# ProPrj_USBuddy_2026-05-01.net
KiCad netlist of a schematic drawn in EasyEDA Pro
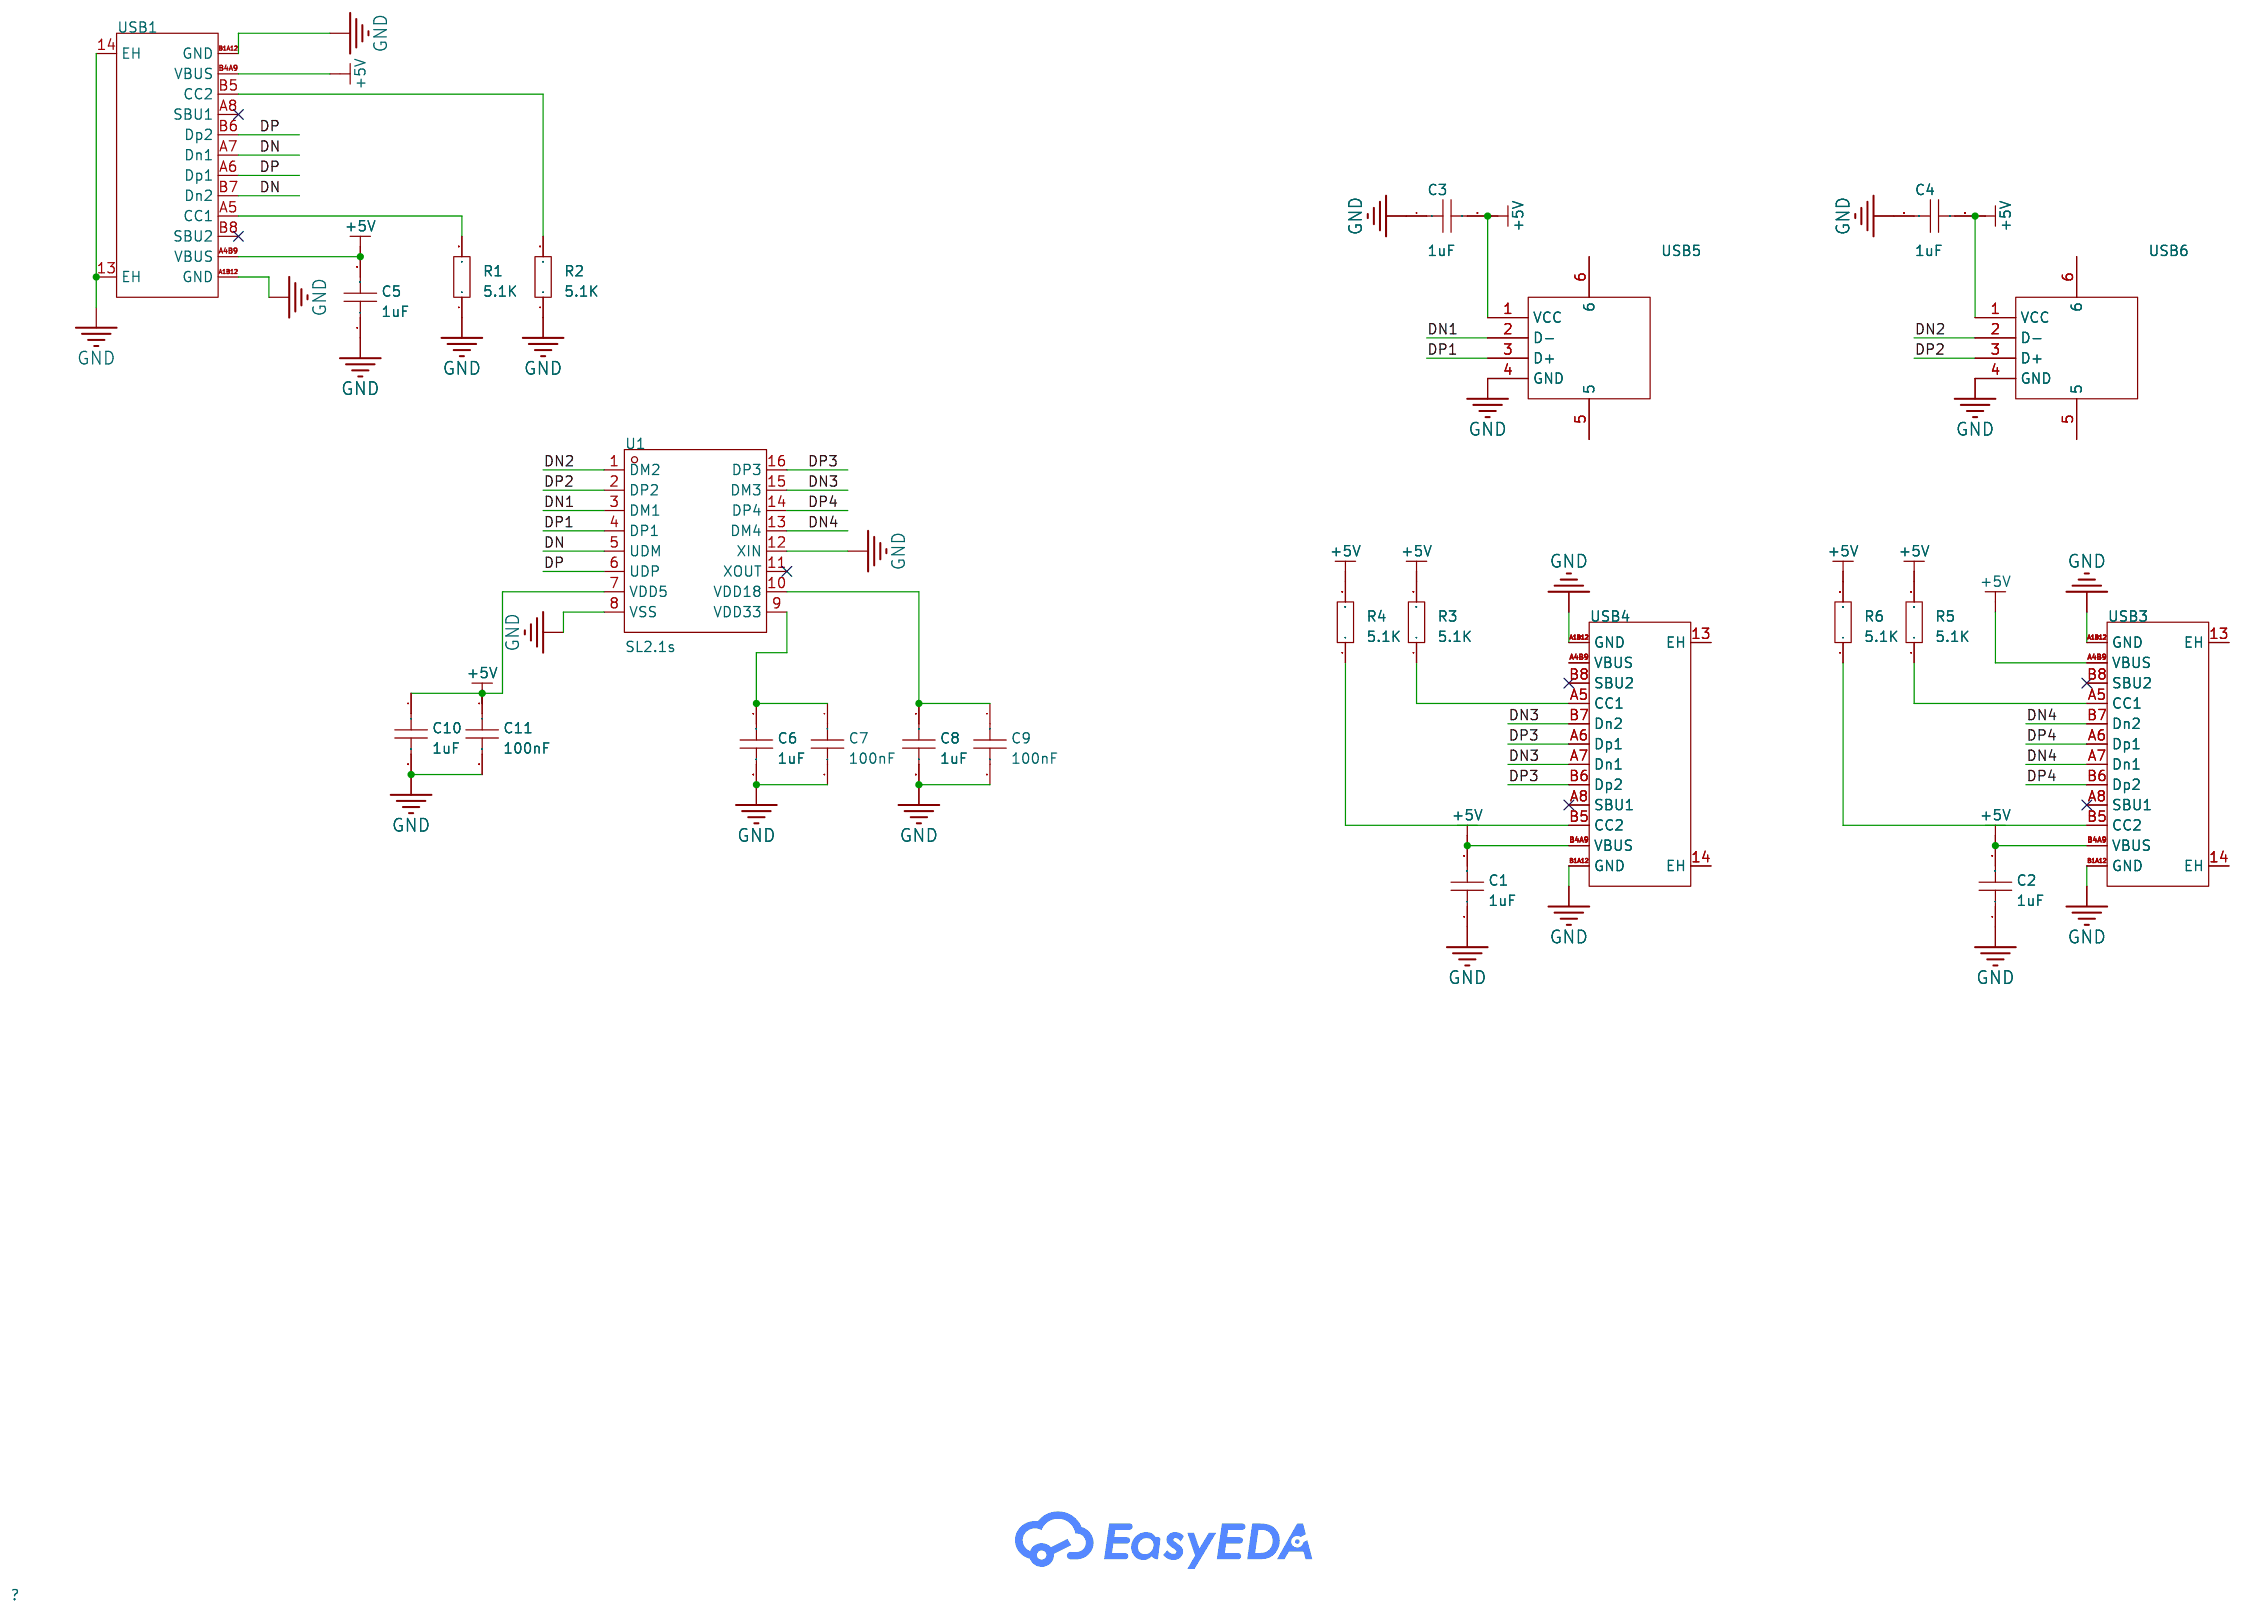
[diagram p0: schematic sheet]

(export (version "E")
  (design (tool "Eeschema 10.0.6"))
  (components
    (comp (ref "C1") (value "1uF") (footprint "easyedapro:C0603") (libsource (lib "easyedapro") (part "CAP")))
    (comp (ref "C2") (value "1uF") (footprint "easyedapro:C0603") (libsource (lib "easyedapro") (part "CAP")))
    (comp (ref "C3") (value "1uF") (footprint "easyedapro:C0603") (libsource (lib "easyedapro") (part "CAP")))
    (comp (ref "C4") (value "1uF") (footprint "easyedapro:C0603") (libsource (lib "easyedapro") (part "CAP")))
    (comp (ref "C5") (value "1uF") (footprint "easyedapro:C0603") (libsource (lib "easyedapro") (part "CAP")))
    (comp (ref "C6") (value "1uF") (footprint "easyedapro:C0603") (libsource (lib "easyedapro") (part "CAP")))
    (comp (ref "C7")
      (value "100nF")
      (footprint "easyedapro:C0603")
      (libsource (lib "easyedapro") (part "CAP"))
    )
    (comp (ref "C8") (value "1uF") (footprint "easyedapro:C0603") (libsource (lib "easyedapro") (part "CAP")))
    (comp (ref "C9")
      (value "100nF")
      (footprint "easyedapro:C0603")
      (libsource (lib "easyedapro") (part "CAP"))
    )
    (comp (ref "C10")
      (value "1uF")
      (footprint "easyedapro:C0603")
      (libsource (lib "easyedapro") (part "CAP"))
    )
    (comp (ref "C11")
      (value "100nF")
      (footprint "easyedapro:C0603")
      (libsource (lib "easyedapro") (part "CAP"))
    )
    (comp (ref "R1")
      (value "5.1K")
      (footprint "easyedapro:R0603")
      (libsource (lib "easyedapro") (part "Res"))
    )
    (comp (ref "R2")
      (value "5.1K")
      (footprint "easyedapro:R0603")
      (libsource (lib "easyedapro") (part "Res"))
    )
    (comp (ref "R3")
      (value "5.1K")
      (footprint "easyedapro:R0603")
      (libsource (lib "easyedapro") (part "Res"))
    )
    (comp (ref "R4")
      (value "5.1K")
      (footprint "easyedapro:R0603")
      (libsource (lib "easyedapro") (part "Res"))
    )
    (comp (ref "R5")
      (value "5.1K")
      (footprint "easyedapro:R0603")
      (libsource (lib "easyedapro") (part "Res"))
    )
    (comp (ref "R6")
      (value "5.1K")
      (footprint "easyedapro:R0603")
      (libsource (lib "easyedapro") (part "Res"))
    )
    (comp (ref "U1")
      (value "SL2.1s")
      (footprint "easyedapro:SSOP-16_L4.6-W2.6-P0.53-LS4.0-BL")
      (fields (field (name "Manufacturer") "CoreChips(和芯润德)"))
      (libsource (lib "easyedapro") (part "SL2.1S"))
    )
    (comp (ref "USB1")
      (value "TYPE-C 16PIN 2MD(073)")
      (footprint "easyedapro:USB-C-SMD_TYPE-C-16PIN-2MD-073")
      (fields (field (name "Manufacturer") "SHOU HAN(首韩)"))
      (libsource (lib "easyedapro") (part "TYPE-C 16PIN 2MD(073)"))
    )
    (comp (ref "USB3")
      (value "TYPE-C 16PIN 2MD(073)")
      (footprint "easyedapro:USB-C-SMD_TYPE-C-16PIN-2MD-073")
      (fields (field (name "Manufacturer") "SHOU HAN(首韩)"))
      (libsource (lib "easyedapro") (part "TYPE-C 16PIN 2MD(073)"))
    )
    (comp (ref "USB4")
      (value "TYPE-C 16PIN 2MD(073)")
      (footprint "easyedapro:USB-C-SMD_TYPE-C-16PIN-2MD-073")
      (fields (field (name "Manufacturer") "SHOU HAN(首韩)"))
      (libsource (lib "easyedapro") (part "TYPE-C 16PIN 2MD(073)"))
    )
    (comp (ref "USB5")
      (value "10.0 QHHTZB6.3")
      (footprint "easyedapro:USB-A-TH_10.0QHHTZB6.3")
      (fields (field (name "Manufacturer") "SHOU HAN(首韩)"))
      (libsource (lib "easyedapro") (part "10.0 QHHTZB6.3"))
    )
    (comp (ref "USB6")
      (value "10.0 QHHTZB6.3")
      (footprint "easyedapro:USB-A-TH_10.0QHHTZB6.3")
      (fields (field (name "Manufacturer") "SHOU HAN(首韩)"))
      (libsource (lib "easyedapro") (part "10.0 QHHTZB6.3"))
    )
  )
  (nets
    (net (code "1") (name "+5V") (class "Default")
      (node (ref "C1") (pin "2") (pinfunction "2_2") (pintype "input"))
      (node (ref "C10") (pin "1") (pinfunction "1_1") (pintype "input"))
      (node (ref "C11") (pin "1") (pinfunction "1_1") (pintype "input"))
      (node (ref "C2") (pin "2") (pinfunction "2_2") (pintype "input"))
      (node (ref "C3") (pin "2") (pinfunction "2_2") (pintype "input"))
      (node (ref "C4") (pin "2") (pinfunction "2_2") (pintype "input"))
      (node (ref "C5") (pin "2") (pinfunction "2_2") (pintype "input"))
      (node (ref "R3") (pin "2") (pinfunction "2_2") (pintype "input"))
      (node (ref "R4") (pin "2") (pinfunction "2_2") (pintype "input"))
      (node (ref "R5") (pin "2") (pinfunction "2_2") (pintype "input"))
      (node (ref "R6") (pin "2") (pinfunction "2_2") (pintype "input"))
      (node (ref "U1") (pin "7") (pinfunction "VDD5_7") (pintype "unspecified"))
      (node (ref "USB1") (pin "A4B9") (pinfunction "VBUS_A4B9") (pintype "unspecified"))
      (node (ref "USB1") (pin "B4A9") (pinfunction "VBUS_B4A9") (pintype "unspecified"))
      (node (ref "USB3") (pin "A4B9") (pinfunction "VBUS_A4B9") (pintype "unspecified"))
      (node (ref "USB3") (pin "B4A9") (pinfunction "VBUS_B4A9") (pintype "unspecified"))
      (node (ref "USB4") (pin "B4A9") (pinfunction "VBUS_B4A9") (pintype "unspecified"))
      (node (ref "USB5") (pin "1") (pinfunction "VCC_1") (pintype "unspecified"))
      (node (ref "USB6") (pin "1") (pinfunction "VCC_1") (pintype "unspecified"))
    )
    (net (code "2") (name "/DN") (class "Default")
      (node (ref "U1") (pin "5") (pinfunction "UDM_5") (pintype "unspecified"))
      (node (ref "USB1") (pin "A7") (pinfunction "Dn1_A7") (pintype "unspecified"))
      (node (ref "USB1") (pin "B7") (pinfunction "Dn2_B7") (pintype "unspecified"))
    )
    (net (code "3") (name "/DN1") (class "Default")
      (node (ref "U1") (pin "3") (pinfunction "DM1_3") (pintype "unspecified"))
      (node (ref "USB5") (pin "2") (pinfunction "D-_2") (pintype "unspecified"))
    )
    (net (code "4") (name "/DN2") (class "Default")
      (node (ref "U1") (pin "1") (pinfunction "DM2_1") (pintype "unspecified"))
      (node (ref "USB6") (pin "2") (pinfunction "D-_2") (pintype "unspecified"))
    )
    (net (code "5") (name "/DN3") (class "Default")
      (node (ref "U1") (pin "15") (pinfunction "DM3_15") (pintype "unspecified"))
      (node (ref "USB4") (pin "A7") (pinfunction "Dn1_A7") (pintype "unspecified"))
      (node (ref "USB4") (pin "B7") (pinfunction "Dn2_B7") (pintype "unspecified"))
    )
    (net (code "6") (name "/DN4") (class "Default")
      (node (ref "U1") (pin "13") (pinfunction "DM4_13") (pintype "unspecified"))
      (node (ref "USB3") (pin "A7") (pinfunction "Dn1_A7") (pintype "unspecified"))
      (node (ref "USB3") (pin "B7") (pinfunction "Dn2_B7") (pintype "unspecified"))
    )
    (net (code "7") (name "/DP") (class "Default")
      (node (ref "U1") (pin "6") (pinfunction "UDP_6") (pintype "unspecified"))
      (node (ref "USB1") (pin "A6") (pinfunction "Dp1_A6") (pintype "unspecified"))
      (node (ref "USB1") (pin "B6") (pinfunction "Dp2_B6") (pintype "unspecified"))
    )
    (net (code "8") (name "/DP1") (class "Default")
      (node (ref "U1") (pin "4") (pinfunction "DP1_4") (pintype "unspecified"))
      (node (ref "USB5") (pin "3") (pinfunction "D+_3") (pintype "unspecified"))
    )
    (net (code "9") (name "/DP2") (class "Default")
      (node (ref "U1") (pin "2") (pinfunction "DP2_2") (pintype "unspecified"))
      (node (ref "USB6") (pin "3") (pinfunction "D+_3") (pintype "unspecified"))
    )
    (net (code "10") (name "/DP3") (class "Default")
      (node (ref "U1") (pin "16") (pinfunction "DP3_16") (pintype "unspecified"))
      (node (ref "USB4") (pin "A6") (pinfunction "Dp1_A6") (pintype "unspecified"))
      (node (ref "USB4") (pin "B6") (pinfunction "Dp2_B6") (pintype "unspecified"))
    )
    (net (code "11") (name "/DP4") (class "Default")
      (node (ref "U1") (pin "14") (pinfunction "DP4_14") (pintype "unspecified"))
      (node (ref "USB3") (pin "A6") (pinfunction "Dp1_A6") (pintype "unspecified"))
      (node (ref "USB3") (pin "B6") (pinfunction "Dp2_B6") (pintype "unspecified"))
    )
    (net (code "12") (name "GND") (class "Default")
      (node (ref "C1") (pin "1") (pinfunction "1_1") (pintype "input"))
      (node (ref "C10") (pin "2") (pinfunction "2_2") (pintype "input"))
      (node (ref "C11") (pin "2") (pinfunction "2_2") (pintype "input"))
      (node (ref "C2") (pin "1") (pinfunction "1_1") (pintype "input"))
      (node (ref "C3") (pin "1") (pinfunction "1_1") (pintype "input"))
      (node (ref "C4") (pin "1") (pinfunction "1_1") (pintype "input"))
      (node (ref "C5") (pin "1") (pinfunction "1_1") (pintype "input"))
      (node (ref "C6") (pin "2") (pinfunction "2_2") (pintype "input"))
      (node (ref "C7") (pin "2") (pinfunction "2_2") (pintype "input"))
      (node (ref "C8") (pin "2") (pinfunction "2_2") (pintype "input"))
      (node (ref "C9") (pin "2") (pinfunction "2_2") (pintype "input"))
      (node (ref "R1") (pin "1") (pinfunction "1_1") (pintype "input"))
      (node (ref "R2") (pin "1") (pinfunction "1_1") (pintype "input"))
      (node (ref "U1") (pin "12") (pinfunction "XIN_12") (pintype "unspecified"))
      (node (ref "U1") (pin "8") (pinfunction "VSS_8") (pintype "unspecified"))
      (node (ref "USB1") (pin "13") (pinfunction "EH_13") (pintype "unspecified"))
      (node (ref "USB1") (pin "14") (pinfunction "EH_14") (pintype "unspecified"))
      (node (ref "USB1") (pin "A1B12") (pinfunction "GND_A1B12") (pintype "unspecified"))
      (node (ref "USB1") (pin "B1A12") (pinfunction "GND_B1A12") (pintype "unspecified"))
      (node (ref "USB3") (pin "A1B12") (pinfunction "GND_A1B12") (pintype "unspecified"))
      (node (ref "USB3") (pin "B1A12") (pinfunction "GND_B1A12") (pintype "unspecified"))
      (node (ref "USB4") (pin "A1B12") (pinfunction "GND_A1B12") (pintype "unspecified"))
      (node (ref "USB4") (pin "B1A12") (pinfunction "GND_B1A12") (pintype "unspecified"))
      (node (ref "USB5") (pin "4") (pinfunction "GND_4") (pintype "unspecified"))
      (node (ref "USB6") (pin "4") (pinfunction "GND_4") (pintype "unspecified"))
    )
    (net (code "13") (name "Net-(U1-VDD18)") (class "Default")
      (node (ref "C8") (pin "1") (pinfunction "1_1") (pintype "input"))
      (node (ref "C9") (pin "1") (pinfunction "1_1") (pintype "input"))
      (node (ref "U1") (pin "10") (pinfunction "VDD18_10") (pintype "unspecified"))
    )
    (net (code "14") (name "Net-(U1-VDD33)") (class "Default")
      (node (ref "C6") (pin "1") (pinfunction "1_1") (pintype "input"))
      (node (ref "C7") (pin "1") (pinfunction "1_1") (pintype "input"))
      (node (ref "U1") (pin "9") (pinfunction "VDD33_9") (pintype "unspecified"))
    )
    (net (code "15") (name "Net-(USB1-CC1)") (class "Default")
      (node (ref "R1") (pin "2") (pinfunction "2_2") (pintype "input"))
      (node (ref "USB1") (pin "A5") (pinfunction "CC1_A5") (pintype "unspecified"))
    )
    (net (code "16") (name "Net-(USB1-CC2)") (class "Default")
      (node (ref "R2") (pin "2") (pinfunction "2_2") (pintype "input"))
      (node (ref "USB1") (pin "B5") (pinfunction "CC2_B5") (pintype "unspecified"))
    )
    (net (code "17") (name "Net-(USB3-CC1)") (class "Default")
      (node (ref "R5") (pin "1") (pinfunction "1_1") (pintype "input"))
      (node (ref "USB3") (pin "A5") (pinfunction "CC1_A5") (pintype "unspecified"))
    )
    (net (code "18") (name "Net-(USB3-CC2)") (class "Default")
      (node (ref "R6") (pin "1") (pinfunction "1_1") (pintype "input"))
      (node (ref "USB3") (pin "B5") (pinfunction "CC2_B5") (pintype "unspecified"))
    )
    (net (code "19") (name "Net-(USB4-CC1)") (class "Default")
      (node (ref "R3") (pin "1") (pinfunction "1_1") (pintype "input"))
      (node (ref "USB4") (pin "A5") (pinfunction "CC1_A5") (pintype "unspecified"))
    )
    (net (code "20") (name "Net-(USB4-CC2)") (class "Default")
      (node (ref "R4") (pin "1") (pinfunction "1_1") (pintype "input"))
      (node (ref "USB4") (pin "B5") (pinfunction "CC2_B5") (pintype "unspecified"))
    )
    (net (code "21") (name "unconnected-(U1-XOUT-Pad11)") (class "Default")
      (node (ref "U1") (pin "11") (pinfunction "XOUT_11") (pintype "unspecified+no_connect"))
    )
    (net (code "22") (name "unconnected-(USB1-SBU1-PadA8)") (class "Default")
      (node (ref "USB1") (pin "A8") (pinfunction "SBU1_A8") (pintype "unspecified+no_connect"))
    )
    (net (code "23") (name "unconnected-(USB1-SBU2-PadB8)") (class "Default")
      (node (ref "USB1") (pin "B8") (pinfunction "SBU2_B8") (pintype "unspecified+no_connect"))
    )
    (net (code "24") (name "unconnected-(USB3-EH-Pad13)") (class "Default")
      (node (ref "USB3") (pin "13") (pinfunction "EH_13") (pintype "unspecified"))
    )
    (net (code "25") (name "unconnected-(USB3-EH-Pad14)") (class "Default")
      (node (ref "USB3") (pin "14") (pinfunction "EH_14") (pintype "unspecified"))
    )
    (net (code "26") (name "unconnected-(USB3-SBU1-PadA8)") (class "Default")
      (node (ref "USB3") (pin "A8") (pinfunction "SBU1_A8") (pintype "unspecified+no_connect"))
    )
    (net (code "27") (name "unconnected-(USB3-SBU2-PadB8)") (class "Default")
      (node (ref "USB3") (pin "B8") (pinfunction "SBU2_B8") (pintype "unspecified+no_connect"))
    )
    (net (code "28") (name "unconnected-(USB4-EH-Pad13)") (class "Default")
      (node (ref "USB4") (pin "13") (pinfunction "EH_13") (pintype "unspecified"))
    )
    (net (code "29") (name "unconnected-(USB4-EH-Pad14)") (class "Default")
      (node (ref "USB4") (pin "14") (pinfunction "EH_14") (pintype "unspecified"))
    )
    (net (code "30") (name "unconnected-(USB4-SBU1-PadA8)") (class "Default")
      (node (ref "USB4") (pin "A8") (pinfunction "SBU1_A8") (pintype "unspecified+no_connect"))
    )
    (net (code "31") (name "unconnected-(USB4-SBU2-PadB8)") (class "Default")
      (node (ref "USB4") (pin "B8") (pinfunction "SBU2_B8") (pintype "unspecified+no_connect"))
    )
    (net (code "32") (name "unconnected-(USB4-VBUS-PadA4B9)") (class "Default")
      (node (ref "USB4") (pin "A4B9") (pinfunction "VBUS_A4B9") (pintype "unspecified"))
    )
    (net (code "33") (name "unconnected-(USB5-Pad5)") (class "Default")
      (node (ref "USB5") (pin "5") (pinfunction "5_5") (pintype "unspecified"))
    )
    (net (code "34") (name "unconnected-(USB5-Pad6)") (class "Default")
      (node (ref "USB5") (pin "6") (pinfunction "6_6") (pintype "unspecified"))
    )
    (net (code "35") (name "unconnected-(USB6-Pad5)") (class "Default")
      (node (ref "USB6") (pin "5") (pinfunction "5_5") (pintype "unspecified"))
    )
    (net (code "36") (name "unconnected-(USB6-Pad6)") (class "Default")
      (node (ref "USB6") (pin "6") (pinfunction "6_6") (pintype "unspecified"))
    )
  )
)
